# Pg1_Top_Sheet_and_Micro.net
KiCad netlist of a schematic drawn in Altium Designer
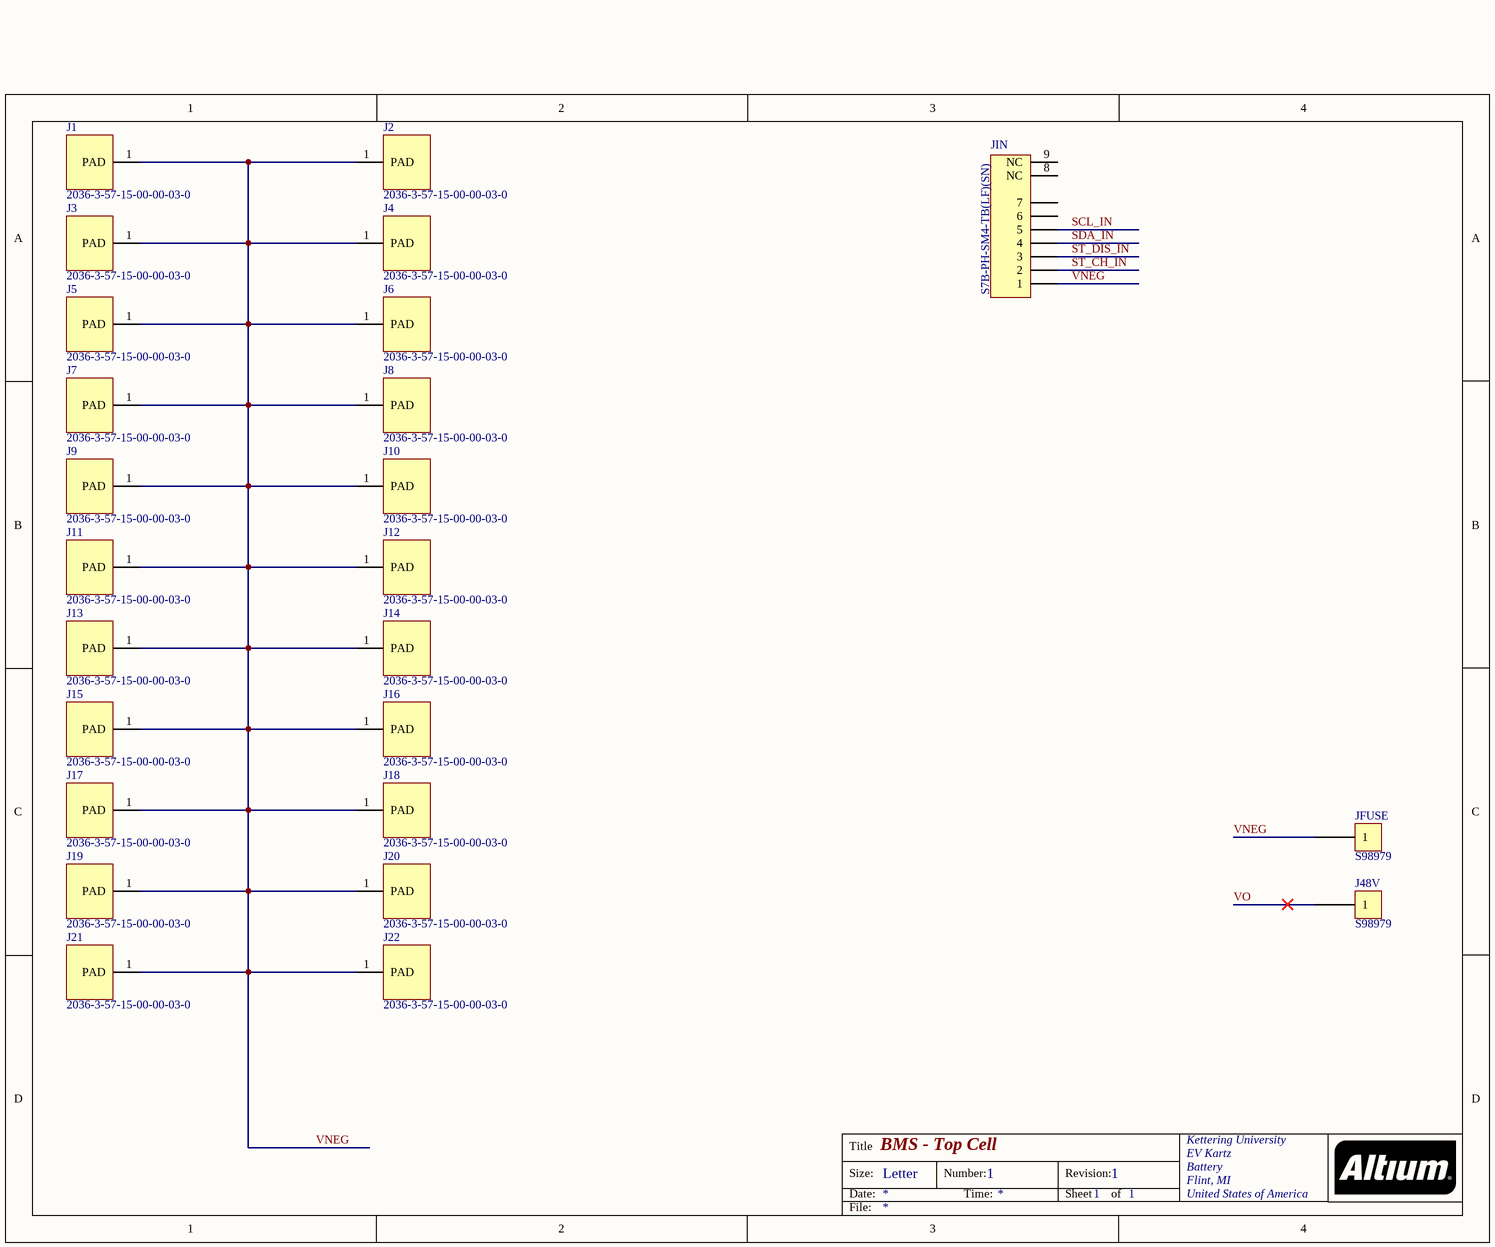
[diagram p0: Pg1 Top Sheet and Micro.SchDoc]

(export (version "E")
  (design (tool "Eeschema 10.0.6"))
  (components
    (comp (ref "J1")
      (value "2036-3-57-15-00-00-03-0")
      (footprint "6mm Pad")
      (description "Hardware, Sprint Contact Surface")
      (libsource (lib "SchLib - EE391 Master") (part "2036-3-57-15-00-00-03-0"))
    )
    (comp (ref "J2")
      (value "2036-3-57-15-00-00-03-0")
      (footprint "6mm Pad")
      (description "Hardware, Sprint Contact Surface")
      (libsource (lib "") (part "2036-3-57-15-00-00-03-0_1"))
    )
    (comp (ref "J3")
      (value "2036-3-57-15-00-00-03-0")
      (footprint "6mm Pad")
      (description "Hardware, Sprint Contact Surface")
      (libsource (lib "SchLib - EE391 Master") (part "2036-3-57-15-00-00-03-0"))
    )
    (comp (ref "J4")
      (value "2036-3-57-15-00-00-03-0")
      (footprint "6mm Pad")
      (description "Hardware, Sprint Contact Surface")
      (libsource (lib "") (part "2036-3-57-15-00-00-03-0_1"))
    )
    (comp (ref "J5")
      (value "2036-3-57-15-00-00-03-0")
      (footprint "6mm Pad")
      (description "Hardware, Sprint Contact Surface")
      (libsource (lib "SchLib - EE391 Master") (part "2036-3-57-15-00-00-03-0"))
    )
    (comp (ref "J6")
      (value "2036-3-57-15-00-00-03-0")
      (footprint "6mm Pad")
      (description "Hardware, Sprint Contact Surface")
      (libsource (lib "") (part "2036-3-57-15-00-00-03-0_1"))
    )
    (comp (ref "J7")
      (value "2036-3-57-15-00-00-03-0")
      (footprint "6mm Pad")
      (description "Hardware, Sprint Contact Surface")
      (libsource (lib "SchLib - EE391 Master") (part "2036-3-57-15-00-00-03-0"))
    )
    (comp (ref "J8")
      (value "2036-3-57-15-00-00-03-0")
      (footprint "6mm Pad")
      (description "Hardware, Sprint Contact Surface")
      (libsource (lib "") (part "2036-3-57-15-00-00-03-0_1"))
    )
    (comp (ref "J9")
      (value "2036-3-57-15-00-00-03-0")
      (footprint "6mm Pad")
      (description "Hardware, Sprint Contact Surface")
      (libsource (lib "SchLib - EE391 Master") (part "2036-3-57-15-00-00-03-0"))
    )
    (comp (ref "J10")
      (value "2036-3-57-15-00-00-03-0")
      (footprint "6mm Pad")
      (description "Hardware, Sprint Contact Surface")
      (libsource (lib "") (part "2036-3-57-15-00-00-03-0_1"))
    )
    (comp (ref "J11")
      (value "2036-3-57-15-00-00-03-0")
      (footprint "6mm Pad")
      (description "Hardware, Sprint Contact Surface")
      (libsource (lib "SchLib - EE391 Master") (part "2036-3-57-15-00-00-03-0"))
    )
    (comp (ref "J12")
      (value "2036-3-57-15-00-00-03-0")
      (footprint "6mm Pad")
      (description "Hardware, Sprint Contact Surface")
      (libsource (lib "") (part "2036-3-57-15-00-00-03-0_1"))
    )
    (comp (ref "J13")
      (value "2036-3-57-15-00-00-03-0")
      (footprint "6mm Pad")
      (description "Hardware, Sprint Contact Surface")
      (libsource (lib "SchLib - EE391 Master") (part "2036-3-57-15-00-00-03-0"))
    )
    (comp (ref "J14")
      (value "2036-3-57-15-00-00-03-0")
      (footprint "6mm Pad")
      (description "Hardware, Sprint Contact Surface")
      (libsource (lib "") (part "2036-3-57-15-00-00-03-0_1"))
    )
    (comp (ref "J15")
      (value "2036-3-57-15-00-00-03-0")
      (footprint "6mm Pad")
      (description "Hardware, Sprint Contact Surface")
      (libsource (lib "SchLib - EE391 Master") (part "2036-3-57-15-00-00-03-0"))
    )
    (comp (ref "J16")
      (value "2036-3-57-15-00-00-03-0")
      (footprint "6mm Pad")
      (description "Hardware, Sprint Contact Surface")
      (libsource (lib "") (part "2036-3-57-15-00-00-03-0_1"))
    )
    (comp (ref "J17")
      (value "2036-3-57-15-00-00-03-0")
      (footprint "6mm Pad")
      (description "Hardware, Sprint Contact Surface")
      (libsource (lib "SchLib - EE391 Master") (part "2036-3-57-15-00-00-03-0"))
    )
    (comp (ref "J18")
      (value "2036-3-57-15-00-00-03-0")
      (footprint "6mm Pad")
      (description "Hardware, Sprint Contact Surface")
      (libsource (lib "") (part "2036-3-57-15-00-00-03-0_1"))
    )
    (comp (ref "J19")
      (value "2036-3-57-15-00-00-03-0")
      (footprint "6mm Pad")
      (description "Hardware, Sprint Contact Surface")
      (libsource (lib "SchLib - EE391 Master") (part "2036-3-57-15-00-00-03-0"))
    )
    (comp (ref "J20")
      (value "2036-3-57-15-00-00-03-0")
      (footprint "6mm Pad")
      (description "Hardware, Sprint Contact Surface")
      (libsource (lib "") (part "2036-3-57-15-00-00-03-0_1"))
    )
    (comp (ref "J21")
      (value "2036-3-57-15-00-00-03-0")
      (footprint "6mm Pad")
      (description "Hardware, Sprint Contact Surface")
      (libsource (lib "SchLib - EE391 Master") (part "2036-3-57-15-00-00-03-0"))
    )
    (comp (ref "J22")
      (value "2036-3-57-15-00-00-03-0")
      (footprint "6mm Pad")
      (description "Hardware, Sprint Contact Surface")
      (libsource (lib "") (part "2036-3-57-15-00-00-03-0_1"))
    )
    (comp (ref "J48V")
      (value "S98979")
      (footprint "S98979")
      (description "Screw Terminal M8, 360A")
      (libsource (lib "Connectors") (part "S98979"))
    )
    (comp (ref "JFUSE")
      (value "S98979")
      (footprint "S98979")
      (description "Screw Terminal M8, 360A")
      (libsource (lib "Connectors") (part "S98979"))
    )
    (comp (ref "JIN")
      (value "S7B-PH-SM4-TB(LF)(SN)")
      (footprint "JST-PH-S7")
      (description "Header, JST, 7-Pin, Right-Angle, PH, Surface Mount")
      (libsource (lib "SchLib - EE391 Master") (part "S7B-PH-SM4-TB(LF)(SN)"))
    )
  )
  (nets
    (net (code "1") (name "/SCL_IN") (class "Default")
      (node (ref "JIN") (pin "5") (pinfunction "5_5") (pintype "passive"))
    )
    (net (code "2") (name "/SDA_IN") (class "Default")
      (node (ref "JIN") (pin "4") (pinfunction "4_4") (pintype "passive"))
    )
    (net (code "3") (name "/ST_CH_IN") (class "Default")
      (node (ref "JIN") (pin "2") (pinfunction "2_2") (pintype "passive"))
    )
    (net (code "4") (name "/ST_DIS_IN") (class "Default")
      (node (ref "JIN") (pin "3") (pinfunction "3_3") (pintype "passive"))
    )
    (net (code "5") (name "/VNEG") (class "Default")
      (node (ref "J1") (pin "1") (pinfunction "PAD_1") (pintype "passive"))
      (node (ref "J10") (pin "1") (pinfunction "PAD_1") (pintype "passive"))
      (node (ref "J11") (pin "1") (pinfunction "PAD_1") (pintype "passive"))
      (node (ref "J12") (pin "1") (pinfunction "PAD_1") (pintype "passive"))
      (node (ref "J13") (pin "1") (pinfunction "PAD_1") (pintype "passive"))
      (node (ref "J14") (pin "1") (pinfunction "PAD_1") (pintype "passive"))
      (node (ref "J15") (pin "1") (pinfunction "PAD_1") (pintype "passive"))
      (node (ref "J16") (pin "1") (pinfunction "PAD_1") (pintype "passive"))
      (node (ref "J17") (pin "1") (pinfunction "PAD_1") (pintype "passive"))
      (node (ref "J18") (pin "1") (pinfunction "PAD_1") (pintype "passive"))
      (node (ref "J19") (pin "1") (pinfunction "PAD_1") (pintype "passive"))
      (node (ref "J2") (pin "1") (pinfunction "PAD_1") (pintype "passive"))
      (node (ref "J20") (pin "1") (pinfunction "PAD_1") (pintype "passive"))
      (node (ref "J21") (pin "1") (pinfunction "PAD_1") (pintype "passive"))
      (node (ref "J22") (pin "1") (pinfunction "PAD_1") (pintype "passive"))
      (node (ref "J3") (pin "1") (pinfunction "PAD_1") (pintype "passive"))
      (node (ref "J4") (pin "1") (pinfunction "PAD_1") (pintype "passive"))
      (node (ref "J5") (pin "1") (pinfunction "PAD_1") (pintype "passive"))
      (node (ref "J6") (pin "1") (pinfunction "PAD_1") (pintype "passive"))
      (node (ref "J7") (pin "1") (pinfunction "PAD_1") (pintype "passive"))
      (node (ref "J8") (pin "1") (pinfunction "PAD_1") (pintype "passive"))
      (node (ref "J9") (pin "1") (pinfunction "PAD_1") (pintype "passive"))
      (node (ref "JFUSE") (pin "1") (pinfunction "1_1") (pintype "passive"))
      (node (ref "JIN") (pin "1") (pinfunction "1_1") (pintype "passive"))
    )
    (net (code "6") (name "/VO") (class "Default")
      (node (ref "J48V") (pin "1") (pinfunction "1_1") (pintype "passive"))
    )
    (net (code "7") (name "unconnected-(JIN-NC-Pad8)") (class "Default")
      (node (ref "JIN") (pin "8") (pinfunction "NC_8") (pintype "tri_state"))
    )
    (net (code "8") (name "unconnected-(JIN-NC-Pad9)") (class "Default")
      (node (ref "JIN") (pin "9") (pinfunction "NC_9") (pintype "tri_state"))
    )
    (net (code "9") (name "unconnected-(JIN-Pad6)") (class "Default")
      (node (ref "JIN") (pin "6") (pinfunction "6_6") (pintype "passive"))
    )
    (net (code "10") (name "unconnected-(JIN-Pad7)") (class "Default")
      (node (ref "JIN") (pin "7") (pinfunction "7_7") (pintype "passive"))
    )
  )
)
